# nhd-4_3-adapter.net
KiCad netlist of a schematic drawn in EAGLE
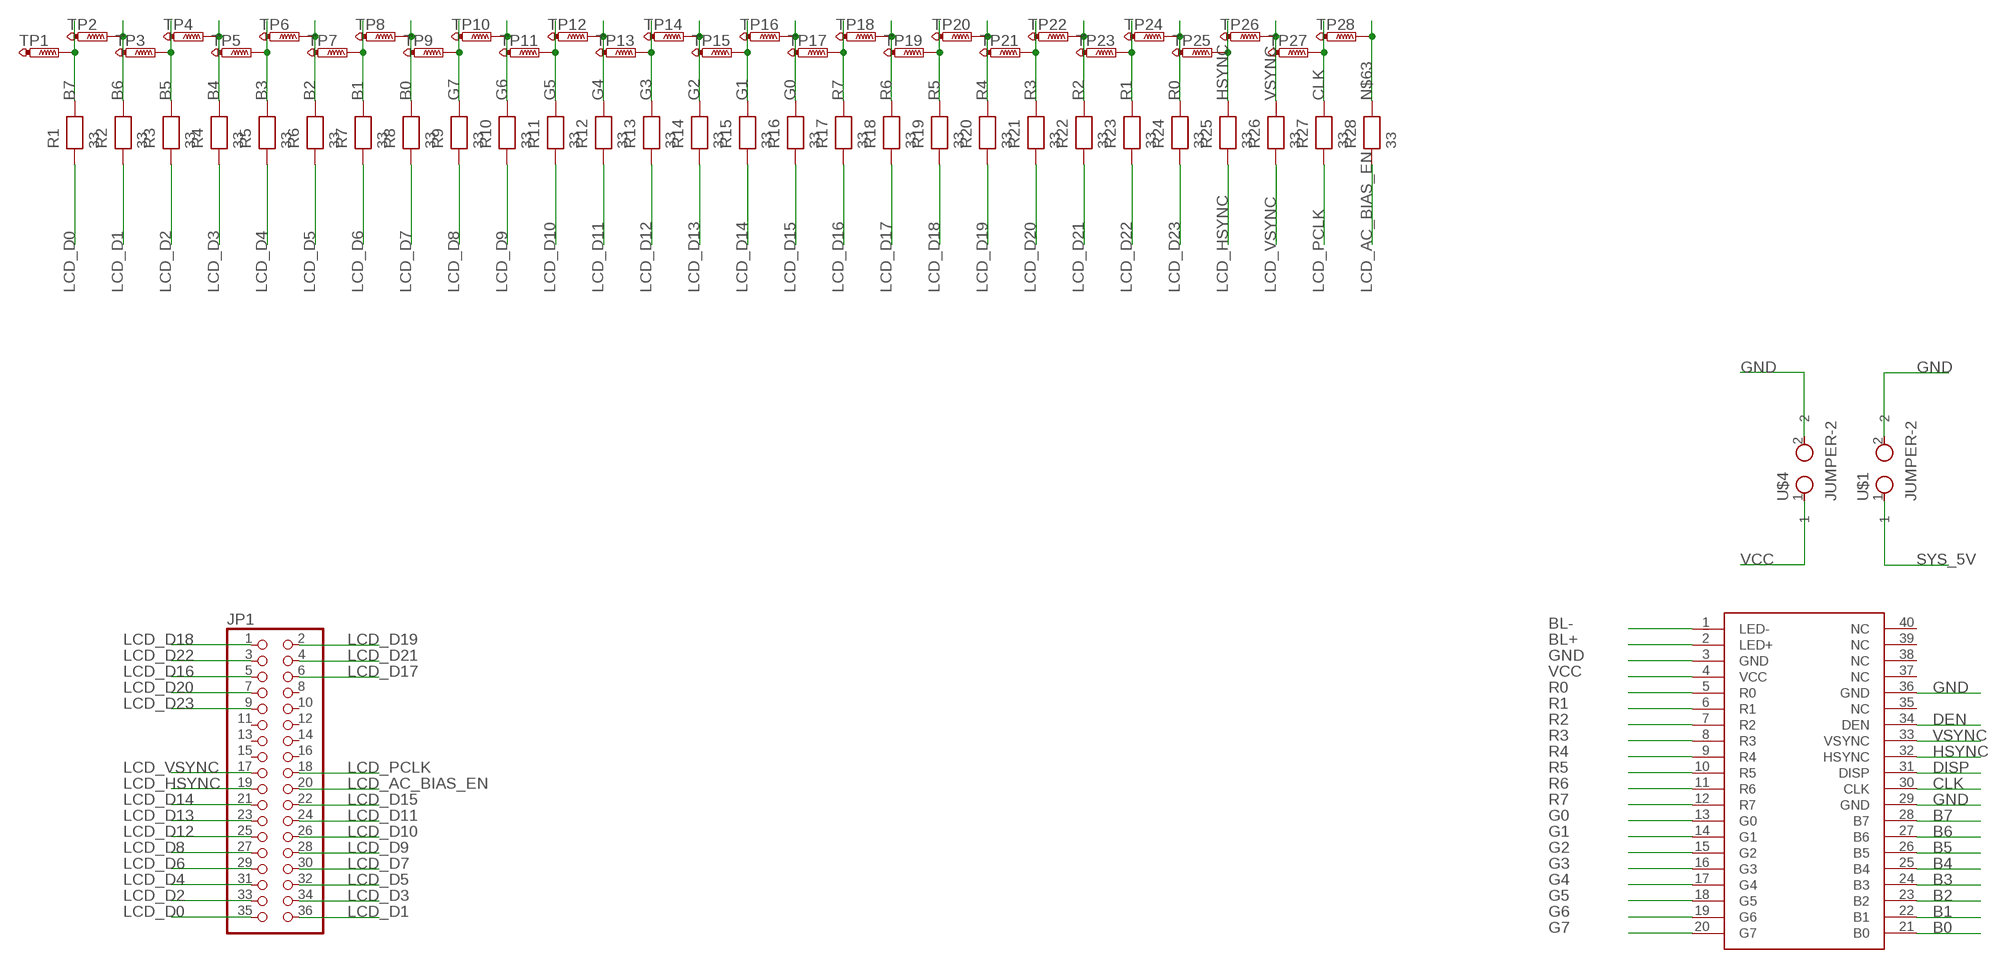
[diagram p0: schematic, sheet 1]
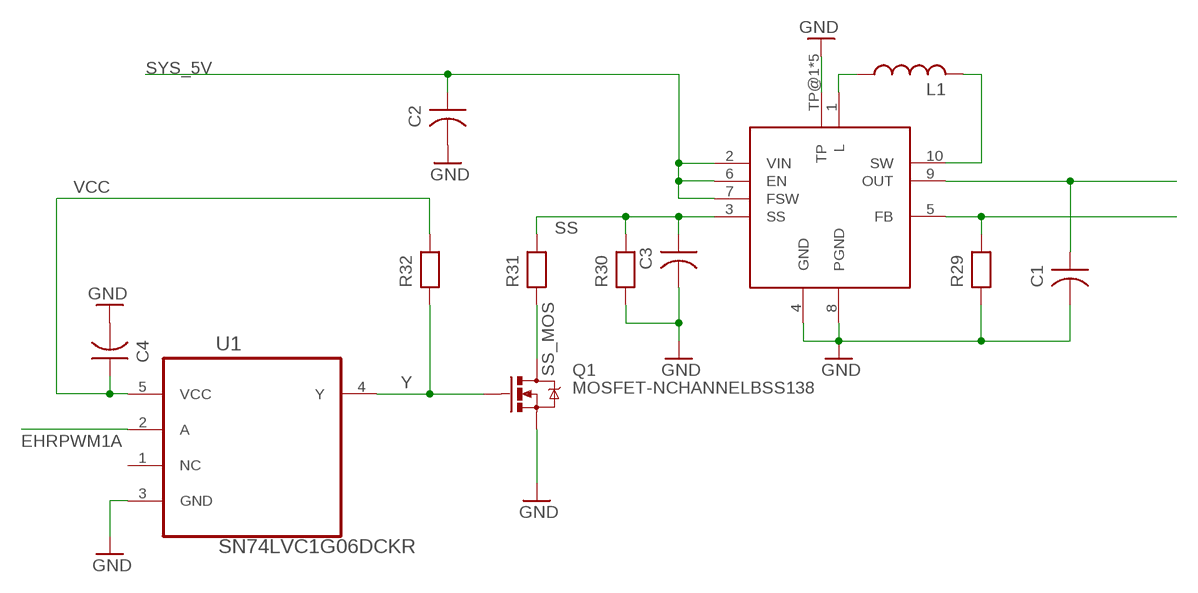
[diagram p1: schematic, sheet 2]

(export (version "E")
  (design (tool "Eeschema 10.0.6"))
  (components
    (comp (ref "JP1")
      (value "PINHD-2X18_2.54")
      (footprint "eagle-import:2X18")
      (libsource (lib "eagle-import") (part "PINHD-2X18_2.54"))
    )
    (comp (ref "R1")
      (value "33")
      (footprint "eagle-import:R0402")
      (libsource (lib "eagle-import") (part "PRES0402LEVEL3"))
    )
    (comp (ref "R2")
      (value "33")
      (footprint "eagle-import:R0402")
      (libsource (lib "eagle-import") (part "PRES0402LEVEL3"))
    )
    (comp (ref "R3")
      (value "33")
      (footprint "eagle-import:R0402")
      (libsource (lib "eagle-import") (part "PRES0402LEVEL3"))
    )
    (comp (ref "R4")
      (value "33")
      (footprint "eagle-import:R0402")
      (libsource (lib "eagle-import") (part "PRES0402LEVEL3"))
    )
    (comp (ref "R5")
      (value "33")
      (footprint "eagle-import:R0402")
      (libsource (lib "eagle-import") (part "PRES0402LEVEL3"))
    )
    (comp (ref "R6")
      (value "33")
      (footprint "eagle-import:R0402")
      (libsource (lib "eagle-import") (part "PRES0402LEVEL3"))
    )
    (comp (ref "R7")
      (value "33")
      (footprint "eagle-import:R0402")
      (libsource (lib "eagle-import") (part "PRES0402LEVEL3"))
    )
    (comp (ref "R8")
      (value "33")
      (footprint "eagle-import:R0402")
      (libsource (lib "eagle-import") (part "PRES0402LEVEL3"))
    )
    (comp (ref "R9")
      (value "33")
      (footprint "eagle-import:R0402")
      (libsource (lib "eagle-import") (part "PRES0402LEVEL3"))
    )
    (comp (ref "R10")
      (value "33")
      (footprint "eagle-import:R0402")
      (libsource (lib "eagle-import") (part "PRES0402LEVEL3"))
    )
    (comp (ref "R11")
      (value "33")
      (footprint "eagle-import:R0402")
      (libsource (lib "eagle-import") (part "PRES0402LEVEL3"))
    )
    (comp (ref "R12")
      (value "33")
      (footprint "eagle-import:R0402")
      (libsource (lib "eagle-import") (part "PRES0402LEVEL3"))
    )
    (comp (ref "R13")
      (value "33")
      (footprint "eagle-import:R0402")
      (libsource (lib "eagle-import") (part "PRES0402LEVEL3"))
    )
    (comp (ref "R14")
      (value "33")
      (footprint "eagle-import:R0402")
      (libsource (lib "eagle-import") (part "PRES0402LEVEL3"))
    )
    (comp (ref "R15")
      (value "33")
      (footprint "eagle-import:R0402")
      (libsource (lib "eagle-import") (part "PRES0402LEVEL3"))
    )
    (comp (ref "R16")
      (value "33")
      (footprint "eagle-import:R0402")
      (libsource (lib "eagle-import") (part "PRES0402LEVEL3"))
    )
    (comp (ref "R17")
      (value "33")
      (footprint "eagle-import:R0402")
      (libsource (lib "eagle-import") (part "PRES0402LEVEL3"))
    )
    (comp (ref "R18")
      (value "33")
      (footprint "eagle-import:R0402")
      (libsource (lib "eagle-import") (part "PRES0402LEVEL3"))
    )
    (comp (ref "R19")
      (value "33")
      (footprint "eagle-import:R0402")
      (libsource (lib "eagle-import") (part "PRES0402LEVEL3"))
    )
    (comp (ref "R20")
      (value "33")
      (footprint "eagle-import:R0402")
      (libsource (lib "eagle-import") (part "PRES0402LEVEL3"))
    )
    (comp (ref "R21")
      (value "33")
      (footprint "eagle-import:R0402")
      (libsource (lib "eagle-import") (part "PRES0402LEVEL3"))
    )
    (comp (ref "R22")
      (value "33")
      (footprint "eagle-import:R0402")
      (libsource (lib "eagle-import") (part "PRES0402LEVEL3"))
    )
    (comp (ref "R23")
      (value "33")
      (footprint "eagle-import:R0402")
      (libsource (lib "eagle-import") (part "PRES0402LEVEL3"))
    )
    (comp (ref "R24")
      (value "33")
      (footprint "eagle-import:R0402")
      (libsource (lib "eagle-import") (part "PRES0402LEVEL3"))
    )
    (comp (ref "R25")
      (value "33")
      (footprint "eagle-import:R0402")
      (libsource (lib "eagle-import") (part "PRES0402LEVEL3"))
    )
    (comp (ref "R26")
      (value "33")
      (footprint "eagle-import:R0402")
      (libsource (lib "eagle-import") (part "PRES0402LEVEL3"))
    )
    (comp (ref "R27")
      (value "33")
      (footprint "eagle-import:R0402")
      (libsource (lib "eagle-import") (part "PRES0402LEVEL3"))
    )
    (comp (ref "R28")
      (value "33")
      (footprint "eagle-import:R0402")
      (libsource (lib "eagle-import") (part "PRES0402LEVEL3"))
    )
    (comp (ref "TFT1")
      (value "NHD-4.3-480272EF-ATXL")
      (footprint "eagle-import:40-PIN_SMD")
      (libsource (lib "eagle-import") (part "NHD-4.3-480272EF-ATXL"))
    )
    (comp (ref "TP1")
      (value "TESTPAD_PTR1TP06R")
      (footprint "eagle-import:TESTPAD_TP06R")
      (libsource (lib "eagle-import") (part "TESTPAD_PTR1TP06R"))
    )
    (comp (ref "TP2")
      (value "TESTPAD_PTR1TP06R")
      (footprint "eagle-import:TESTPAD_TP06R")
      (libsource (lib "eagle-import") (part "TESTPAD_PTR1TP06R"))
    )
    (comp (ref "TP3")
      (value "TESTPAD_PTR1TP06R")
      (footprint "eagle-import:TESTPAD_TP06R")
      (libsource (lib "eagle-import") (part "TESTPAD_PTR1TP06R"))
    )
    (comp (ref "TP4")
      (value "TESTPAD_PTR1TP06R")
      (footprint "eagle-import:TESTPAD_TP06R")
      (libsource (lib "eagle-import") (part "TESTPAD_PTR1TP06R"))
    )
    (comp (ref "TP5")
      (value "TESTPAD_PTR1TP06R")
      (footprint "eagle-import:TESTPAD_TP06R")
      (libsource (lib "eagle-import") (part "TESTPAD_PTR1TP06R"))
    )
    (comp (ref "TP6")
      (value "TESTPAD_PTR1TP06R")
      (footprint "eagle-import:TESTPAD_TP06R")
      (libsource (lib "eagle-import") (part "TESTPAD_PTR1TP06R"))
    )
    (comp (ref "TP7")
      (value "TESTPAD_PTR1TP06R")
      (footprint "eagle-import:TESTPAD_TP06R")
      (libsource (lib "eagle-import") (part "TESTPAD_PTR1TP06R"))
    )
    (comp (ref "TP8")
      (value "TESTPAD_PTR1TP06R")
      (footprint "eagle-import:TESTPAD_TP06R")
      (libsource (lib "eagle-import") (part "TESTPAD_PTR1TP06R"))
    )
    (comp (ref "TP9")
      (value "TESTPAD_PTR1TP06R")
      (footprint "eagle-import:TESTPAD_TP06R")
      (libsource (lib "eagle-import") (part "TESTPAD_PTR1TP06R"))
    )
    (comp (ref "TP10")
      (value "TESTPAD_PTR1TP06R")
      (footprint "eagle-import:TESTPAD_TP06R")
      (libsource (lib "eagle-import") (part "TESTPAD_PTR1TP06R"))
    )
    (comp (ref "TP11")
      (value "TESTPAD_PTR1TP06R")
      (footprint "eagle-import:TESTPAD_TP06R")
      (libsource (lib "eagle-import") (part "TESTPAD_PTR1TP06R"))
    )
    (comp (ref "TP12")
      (value "TESTPAD_PTR1TP06R")
      (footprint "eagle-import:TESTPAD_TP06R")
      (libsource (lib "eagle-import") (part "TESTPAD_PTR1TP06R"))
    )
    (comp (ref "TP13")
      (value "TESTPAD_PTR1TP06R")
      (footprint "eagle-import:TESTPAD_TP06R")
      (libsource (lib "eagle-import") (part "TESTPAD_PTR1TP06R"))
    )
    (comp (ref "TP14")
      (value "TESTPAD_PTR1TP06R")
      (footprint "eagle-import:TESTPAD_TP06R")
      (libsource (lib "eagle-import") (part "TESTPAD_PTR1TP06R"))
    )
    (comp (ref "TP15")
      (value "TESTPAD_PTR1TP06R")
      (footprint "eagle-import:TESTPAD_TP06R")
      (libsource (lib "eagle-import") (part "TESTPAD_PTR1TP06R"))
    )
    (comp (ref "TP16")
      (value "TESTPAD_PTR1TP06R")
      (footprint "eagle-import:TESTPAD_TP06R")
      (libsource (lib "eagle-import") (part "TESTPAD_PTR1TP06R"))
    )
    (comp (ref "TP17")
      (value "TESTPAD_PTR1TP06R")
      (footprint "eagle-import:TESTPAD_TP06R")
      (libsource (lib "eagle-import") (part "TESTPAD_PTR1TP06R"))
    )
    (comp (ref "TP18")
      (value "TESTPAD_PTR1TP06R")
      (footprint "eagle-import:TESTPAD_TP06R")
      (libsource (lib "eagle-import") (part "TESTPAD_PTR1TP06R"))
    )
    (comp (ref "TP19")
      (value "TESTPAD_PTR1TP06R")
      (footprint "eagle-import:TESTPAD_TP06R")
      (libsource (lib "eagle-import") (part "TESTPAD_PTR1TP06R"))
    )
    (comp (ref "TP20")
      (value "TESTPAD_PTR1TP06R")
      (footprint "eagle-import:TESTPAD_TP06R")
      (libsource (lib "eagle-import") (part "TESTPAD_PTR1TP06R"))
    )
    (comp (ref "TP21")
      (value "TESTPAD_PTR1TP06R")
      (footprint "eagle-import:TESTPAD_TP06R")
      (libsource (lib "eagle-import") (part "TESTPAD_PTR1TP06R"))
    )
    (comp (ref "TP22")
      (value "TESTPAD_PTR1TP06R")
      (footprint "eagle-import:TESTPAD_TP06R")
      (libsource (lib "eagle-import") (part "TESTPAD_PTR1TP06R"))
    )
    (comp (ref "TP23")
      (value "TESTPAD_PTR1TP06R")
      (footprint "eagle-import:TESTPAD_TP06R")
      (libsource (lib "eagle-import") (part "TESTPAD_PTR1TP06R"))
    )
    (comp (ref "TP24")
      (value "TESTPAD_PTR1TP06R")
      (footprint "eagle-import:TESTPAD_TP06R")
      (libsource (lib "eagle-import") (part "TESTPAD_PTR1TP06R"))
    )
    (comp (ref "TP25")
      (value "TESTPAD_PTR1TP06R")
      (footprint "eagle-import:TESTPAD_TP06R")
      (libsource (lib "eagle-import") (part "TESTPAD_PTR1TP06R"))
    )
    (comp (ref "TP26")
      (value "TESTPAD_PTR1TP06R")
      (footprint "eagle-import:TESTPAD_TP06R")
      (libsource (lib "eagle-import") (part "TESTPAD_PTR1TP06R"))
    )
    (comp (ref "TP27")
      (value "TESTPAD_PTR1TP06R")
      (footprint "eagle-import:TESTPAD_TP06R")
      (libsource (lib "eagle-import") (part "TESTPAD_PTR1TP06R"))
    )
    (comp (ref "TP28")
      (value "TESTPAD_PTR1TP06R")
      (footprint "eagle-import:TESTPAD_TP06R")
      (libsource (lib "eagle-import") (part "TESTPAD_PTR1TP06R"))
    )
    (comp (ref "U$1")
      (value "JUMPER-2")
      (footprint "eagle-import:1X02")
      (libsource (lib "eagle-import") (part "JUMPER-2"))
    )
    (comp (ref "U$4")
      (value "JUMPER-2")
      (footprint "eagle-import:1X02")
      (libsource (lib "eagle-import") (part "JUMPER-2"))
    )
    (comp (ref "C1")
      (value "PCAP0805LEVEL3")
      (footprint "eagle-import:R0805")
      (libsource (lib "eagle-import") (part "PCAP0805LEVEL3"))
    )
    (comp (ref "C2")
      (value "PCAP0805LEVEL3")
      (footprint "eagle-import:R0805")
      (libsource (lib "eagle-import") (part "PCAP0805LEVEL3"))
    )
    (comp (ref "C3")
      (value "PCAP0603LEVEL3")
      (footprint "eagle-import:R0603")
      (libsource (lib "eagle-import") (part "PCAP0603LEVEL3"))
    )
    (comp (ref "C4")
      (value "PCAP0603LEVEL3")
      (footprint "eagle-import:R0603")
      (libsource (lib "eagle-import") (part "PCAP0603LEVEL3"))
    )
    (comp (ref "L1")
      (value "L-US")
      (footprint "eagle-import:VLCF4018-2")
      (libsource (lib "eagle-import") (part "L-US"))
    )
    (comp (ref "Q1")
      (value "MOSFET-NCHANNELBSS138")
      (footprint "eagle-import:SOT23")
      (libsource (lib "eagle-import") (part "MOSFET-NCHANNELBSS138"))
    )
    (comp (ref "R29")
      (value "PRES0603LEVEL3")
      (footprint "eagle-import:R0603")
      (libsource (lib "eagle-import") (part "PRES0603LEVEL3"))
    )
    (comp (ref "R30")
      (value "PRES0603LEVEL3")
      (footprint "eagle-import:R0603")
      (libsource (lib "eagle-import") (part "PRES0603LEVEL3"))
    )
    (comp (ref "R31")
      (value "PRES0603LEVEL3")
      (footprint "eagle-import:R0603")
      (libsource (lib "eagle-import") (part "PRES0603LEVEL3"))
    )
    (comp (ref "R32")
      (value "PRES0603LEVEL3")
      (footprint "eagle-import:R0603")
      (libsource (lib "eagle-import") (part "PRES0603LEVEL3"))
    )
    (comp (ref "U$2")
      (value "TPS61080")
      (footprint "eagle-import:VSON-10")
      (libsource (lib "eagle-import") (part "TPS61080"))
    )
    (comp (ref "U1")
      (value "SN74LVC1G06DCKR")
      (footprint "eagle-import:SOT65P210X110-5N")
      (libsource (lib "eagle-import") (part "SN74LVC1G06DCKR"))
    )
  )
  (nets
    (net (code "1") (name "B0") (class "Default")
      (node (ref "R8") (pin "P$2") (pinfunction "P$2_P$2") (pintype "bidirectional"))
      (node (ref "TFT1") (pin "21") (pinfunction "B0_21") (pintype "bidirectional"))
      (node (ref "TP8") (pin "TP") (pinfunction "TP_TP") (pintype "input"))
    )
    (net (code "2") (name "B1") (class "Default")
      (node (ref "R7") (pin "P$2") (pinfunction "P$2_P$2") (pintype "bidirectional"))
      (node (ref "TFT1") (pin "22") (pinfunction "B1_22") (pintype "bidirectional"))
      (node (ref "TP7") (pin "TP") (pinfunction "TP_TP") (pintype "input"))
    )
    (net (code "3") (name "B2") (class "Default")
      (node (ref "R6") (pin "P$2") (pinfunction "P$2_P$2") (pintype "bidirectional"))
      (node (ref "TFT1") (pin "23") (pinfunction "B2_23") (pintype "bidirectional"))
      (node (ref "TP6") (pin "TP") (pinfunction "TP_TP") (pintype "input"))
    )
    (net (code "4") (name "B3") (class "Default")
      (node (ref "R5") (pin "P$2") (pinfunction "P$2_P$2") (pintype "bidirectional"))
      (node (ref "TFT1") (pin "24") (pinfunction "B3_24") (pintype "bidirectional"))
      (node (ref "TP5") (pin "TP") (pinfunction "TP_TP") (pintype "input"))
    )
    (net (code "5") (name "B4") (class "Default")
      (node (ref "R4") (pin "P$2") (pinfunction "P$2_P$2") (pintype "bidirectional"))
      (node (ref "TFT1") (pin "25") (pinfunction "B4_25") (pintype "bidirectional"))
      (node (ref "TP4") (pin "TP") (pinfunction "TP_TP") (pintype "input"))
    )
    (net (code "6") (name "B5") (class "Default")
      (node (ref "R3") (pin "P$2") (pinfunction "P$2_P$2") (pintype "bidirectional"))
      (node (ref "TFT1") (pin "26") (pinfunction "B5_26") (pintype "bidirectional"))
      (node (ref "TP3") (pin "TP") (pinfunction "TP_TP") (pintype "input"))
    )
    (net (code "7") (name "B6") (class "Default")
      (node (ref "R2") (pin "P$2") (pinfunction "P$2_P$2") (pintype "bidirectional"))
      (node (ref "TFT1") (pin "27") (pinfunction "B6_27") (pintype "bidirectional"))
      (node (ref "TP2") (pin "TP") (pinfunction "TP_TP") (pintype "input"))
    )
    (net (code "8") (name "B7") (class "Default")
      (node (ref "R1") (pin "P$2") (pinfunction "P$2_P$2") (pintype "bidirectional"))
      (node (ref "TFT1") (pin "28") (pinfunction "B7_28") (pintype "bidirectional"))
      (node (ref "TP1") (pin "TP") (pinfunction "TP_TP") (pintype "input"))
    )
    (net (code "9") (name "BL+") (class "Default")
      (node (ref "C1") (pin "P$2") (pinfunction "P$2_P$2") (pintype "bidirectional"))
      (node (ref "TFT1") (pin "2") (pinfunction "LED+_2") (pintype "bidirectional"))
      (node (ref "U$2") (pin "9") (pinfunction "OUT_9") (pintype "bidirectional"))
    )
    (net (code "10") (name "BL-") (class "Default")
      (node (ref "R29") (pin "P$2") (pinfunction "P$2_P$2") (pintype "bidirectional"))
      (node (ref "TFT1") (pin "1") (pinfunction "LED-_1") (pintype "bidirectional"))
      (node (ref "U$2") (pin "5") (pinfunction "FB_5") (pintype "bidirectional"))
    )
    (net (code "11") (name "CLK") (class "Default")
      (node (ref "R27") (pin "P$2") (pinfunction "P$2_P$2") (pintype "bidirectional"))
      (node (ref "TFT1") (pin "30") (pinfunction "CLK_30") (pintype "bidirectional"))
      (node (ref "TP27") (pin "TP") (pinfunction "TP_TP") (pintype "input"))
    )
    (net (code "12") (name "DEN") (class "Default")
      (node (ref "TFT1") (pin "34") (pinfunction "DEN_34") (pintype "bidirectional"))
    )
    (net (code "13") (name "DISP") (class "Default")
      (node (ref "TFT1") (pin "31") (pinfunction "DISP_31") (pintype "bidirectional"))
    )
    (net (code "14") (name "EHRPWM1A") (class "Default")
      (node (ref "U1") (pin "2") (pinfunction "A_2") (pintype "input"))
    )
    (net (code "15") (name "G0") (class "Default")
      (node (ref "R16") (pin "P$2") (pinfunction "P$2_P$2") (pintype "bidirectional"))
      (node (ref "TFT1") (pin "13") (pinfunction "G0_13") (pintype "bidirectional"))
      (node (ref "TP16") (pin "TP") (pinfunction "TP_TP") (pintype "input"))
    )
    (net (code "16") (name "G1") (class "Default")
      (node (ref "R15") (pin "P$2") (pinfunction "P$2_P$2") (pintype "bidirectional"))
      (node (ref "TFT1") (pin "14") (pinfunction "G1_14") (pintype "bidirectional"))
      (node (ref "TP15") (pin "TP") (pinfunction "TP_TP") (pintype "input"))
    )
    (net (code "17") (name "G2") (class "Default")
      (node (ref "R14") (pin "P$2") (pinfunction "P$2_P$2") (pintype "bidirectional"))
      (node (ref "TFT1") (pin "15") (pinfunction "G2_15") (pintype "bidirectional"))
      (node (ref "TP14") (pin "TP") (pinfunction "TP_TP") (pintype "input"))
    )
    (net (code "18") (name "G3") (class "Default")
      (node (ref "R13") (pin "P$2") (pinfunction "P$2_P$2") (pintype "bidirectional"))
      (node (ref "TFT1") (pin "16") (pinfunction "G3_16") (pintype "bidirectional"))
      (node (ref "TP13") (pin "TP") (pinfunction "TP_TP") (pintype "input"))
    )
    (net (code "19") (name "G4") (class "Default")
      (node (ref "R12") (pin "P$2") (pinfunction "P$2_P$2") (pintype "bidirectional"))
      (node (ref "TFT1") (pin "17") (pinfunction "G4_17") (pintype "bidirectional"))
      (node (ref "TP12") (pin "TP") (pinfunction "TP_TP") (pintype "input"))
    )
    (net (code "20") (name "G5") (class "Default")
      (node (ref "R11") (pin "P$2") (pinfunction "P$2_P$2") (pintype "bidirectional"))
      (node (ref "TFT1") (pin "18") (pinfunction "G5_18") (pintype "bidirectional"))
      (node (ref "TP11") (pin "TP") (pinfunction "TP_TP") (pintype "input"))
    )
    (net (code "21") (name "G6") (class "Default")
      (node (ref "R10") (pin "P$2") (pinfunction "P$2_P$2") (pintype "bidirectional"))
      (node (ref "TFT1") (pin "19") (pinfunction "G6_19") (pintype "bidirectional"))
      (node (ref "TP10") (pin "TP") (pinfunction "TP_TP") (pintype "input"))
    )
    (net (code "22") (name "G7") (class "Default")
      (node (ref "R9") (pin "P$2") (pinfunction "P$2_P$2") (pintype "bidirectional"))
      (node (ref "TFT1") (pin "20") (pinfunction "G7_20") (pintype "bidirectional"))
      (node (ref "TP9") (pin "TP") (pinfunction "TP_TP") (pintype "input"))
    )
    (net (code "23") (name "GND") (class "Default")
      (node (ref "C1") (pin "P$1") (pinfunction "P$1_P$1") (pintype "bidirectional"))
      (node (ref "C2") (pin "P$1") (pinfunction "P$1_P$1") (pintype "bidirectional"))
      (node (ref "C3") (pin "P$1") (pinfunction "P$1_P$1") (pintype "bidirectional"))
      (node (ref "C4") (pin "P$1") (pinfunction "P$1_P$1") (pintype "bidirectional"))
      (node (ref "Q1") (pin "2") (pinfunction "S_2") (pintype "passive"))
      (node (ref "R29") (pin "P$1") (pinfunction "P$1_P$1") (pintype "bidirectional"))
      (node (ref "R30") (pin "P$1") (pinfunction "P$1_P$1") (pintype "bidirectional"))
      (node (ref "TFT1") (pin "29") (pinfunction "GND_29") (pintype "bidirectional"))
      (node (ref "TFT1") (pin "3") (pinfunction "GND_3") (pintype "bidirectional"))
      (node (ref "TFT1") (pin "36") (pinfunction "GND_36") (pintype "bidirectional"))
      (node (ref "U$1") (pin "2") (pinfunction "2_2") (pintype "bidirectional"))
      (node (ref "U$2") (pin "4") (pinfunction "GND_4") (pintype "bidirectional"))
      (node (ref "U$2") (pin "8") (pinfunction "PGND_8") (pintype "bidirectional"))
      (node (ref "U$2") (pin "TP@1") (pinfunction "TP_TP@1") (pintype "bidirectional"))
      (node (ref "U$2") (pin "TP@2") (pinfunction "TP_TP@2") (pintype "bidirectional"))
      (node (ref "U$2") (pin "TP@3") (pinfunction "TP_TP@3") (pintype "bidirectional"))
      (node (ref "U$2") (pin "TP@4") (pinfunction "TP_TP@4") (pintype "bidirectional"))
      (node (ref "U$2") (pin "TP@5") (pinfunction "TP_TP@5") (pintype "bidirectional"))
      (node (ref "U$4") (pin "2") (pinfunction "2_2") (pintype "bidirectional"))
      (node (ref "U1") (pin "3") (pinfunction "GND_3") (pintype "passive"))
    )
    (net (code "24") (name "HSYNC") (class "Default")
      (node (ref "R25") (pin "P$2") (pinfunction "P$2_P$2") (pintype "bidirectional"))
      (node (ref "TFT1") (pin "32") (pinfunction "HSYNC_32") (pintype "bidirectional"))
      (node (ref "TP25") (pin "TP") (pinfunction "TP_TP") (pintype "input"))
    )
    (net (code "25") (name "LCD_AC_BIAS_EN") (class "Default")
      (node (ref "JP1") (pin "20") (pinfunction "20_20") (pintype "passive"))
      (node (ref "R28") (pin "P$1") (pinfunction "P$1_P$1") (pintype "bidirectional"))
    )
    (net (code "26") (name "LCD_D0") (class "Default")
      (node (ref "JP1") (pin "35") (pinfunction "35_35") (pintype "passive"))
      (node (ref "R1") (pin "P$1") (pinfunction "P$1_P$1") (pintype "bidirectional"))
    )
    (net (code "27") (name "LCD_D1") (class "Default")
      (node (ref "JP1") (pin "36") (pinfunction "36_36") (pintype "passive"))
      (node (ref "R2") (pin "P$1") (pinfunction "P$1_P$1") (pintype "bidirectional"))
    )
    (net (code "28") (name "LCD_D2") (class "Default")
      (node (ref "JP1") (pin "33") (pinfunction "33_33") (pintype "passive"))
      (node (ref "R3") (pin "P$1") (pinfunction "P$1_P$1") (pintype "bidirectional"))
    )
    (net (code "29") (name "LCD_D3") (class "Default")
      (node (ref "JP1") (pin "34") (pinfunction "34_34") (pintype "passive"))
      (node (ref "R4") (pin "P$1") (pinfunction "P$1_P$1") (pintype "bidirectional"))
    )
    (net (code "30") (name "LCD_D4") (class "Default")
      (node (ref "JP1") (pin "31") (pinfunction "31_31") (pintype "passive"))
      (node (ref "R5") (pin "P$1") (pinfunction "P$1_P$1") (pintype "bidirectional"))
    )
    (net (code "31") (name "LCD_D5") (class "Default")
      (node (ref "JP1") (pin "32") (pinfunction "32_32") (pintype "passive"))
      (node (ref "R6") (pin "P$1") (pinfunction "P$1_P$1") (pintype "bidirectional"))
    )
    (net (code "32") (name "LCD_D6") (class "Default")
      (node (ref "JP1") (pin "29") (pinfunction "29_29") (pintype "passive"))
      (node (ref "R7") (pin "P$1") (pinfunction "P$1_P$1") (pintype "bidirectional"))
    )
    (net (code "33") (name "LCD_D7") (class "Default")
      (node (ref "JP1") (pin "30") (pinfunction "30_30") (pintype "passive"))
      (node (ref "R8") (pin "P$1") (pinfunction "P$1_P$1") (pintype "bidirectional"))
    )
    (net (code "34") (name "LCD_D8") (class "Default")
      (node (ref "JP1") (pin "27") (pinfunction "27_27") (pintype "passive"))
      (node (ref "R9") (pin "P$1") (pinfunction "P$1_P$1") (pintype "bidirectional"))
    )
    (net (code "35") (name "LCD_D9") (class "Default")
      (node (ref "JP1") (pin "28") (pinfunction "28_28") (pintype "passive"))
      (node (ref "R10") (pin "P$1") (pinfunction "P$1_P$1") (pintype "bidirectional"))
    )
    (net (code "36") (name "LCD_D10") (class "Default")
      (node (ref "JP1") (pin "26") (pinfunction "26_26") (pintype "passive"))
      (node (ref "R11") (pin "P$1") (pinfunction "P$1_P$1") (pintype "bidirectional"))
    )
    (net (code "37") (name "LCD_D11") (class "Default")
      (node (ref "JP1") (pin "24") (pinfunction "24_24") (pintype "passive"))
      (node (ref "R12") (pin "P$1") (pinfunction "P$1_P$1") (pintype "bidirectional"))
    )
    (net (code "38") (name "LCD_D12") (class "Default")
      (node (ref "JP1") (pin "25") (pinfunction "25_25") (pintype "passive"))
      (node (ref "R13") (pin "P$1") (pinfunction "P$1_P$1") (pintype "bidirectional"))
    )
    (net (code "39") (name "LCD_D13") (class "Default")
      (node (ref "JP1") (pin "23") (pinfunction "23_23") (pintype "passive"))
      (node (ref "R14") (pin "P$1") (pinfunction "P$1_P$1") (pintype "bidirectional"))
    )
    (net (code "40") (name "LCD_D14") (class "Default")
      (node (ref "JP1") (pin "21") (pinfunction "21_21") (pintype "passive"))
      (node (ref "R15") (pin "P$1") (pinfunction "P$1_P$1") (pintype "bidirectional"))
    )
    (net (code "41") (name "LCD_D15") (class "Default")
      (node (ref "JP1") (pin "22") (pinfunction "22_22") (pintype "passive"))
      (node (ref "R16") (pin "P$1") (pinfunction "P$1_P$1") (pintype "bidirectional"))
    )
    (net (code "42") (name "LCD_D16") (class "Default")
      (node (ref "JP1") (pin "5") (pinfunction "5_5") (pintype "passive"))
      (node (ref "R17") (pin "P$1") (pinfunction "P$1_P$1") (pintype "bidirectional"))
    )
    (net (code "43") (name "LCD_D17") (class "Default")
      (node (ref "JP1") (pin "6") (pinfunction "6_6") (pintype "passive"))
      (node (ref "R18") (pin "P$1") (pinfunction "P$1_P$1") (pintype "bidirectional"))
    )
    (net (code "44") (name "LCD_D18") (class "Default")
      (node (ref "JP1") (pin "1") (pinfunction "1_1") (pintype "passive"))
      (node (ref "R19") (pin "P$1") (pinfunction "P$1_P$1") (pintype "bidirectional"))
    )
    (net (code "45") (name "LCD_D19") (class "Default")
      (node (ref "JP1") (pin "2") (pinfunction "2_2") (pintype "passive"))
      (node (ref "R20") (pin "P$1") (pinfunction "P$1_P$1") (pintype "bidirectional"))
    )
    (net (code "46") (name "LCD_D20") (class "Default")
      (node (ref "JP1") (pin "7") (pinfunction "7_7") (pintype "passive"))
      (node (ref "R21") (pin "P$1") (pinfunction "P$1_P$1") (pintype "bidirectional"))
    )
    (net (code "47") (name "LCD_D21") (class "Default")
      (node (ref "JP1") (pin "4") (pinfunction "4_4") (pintype "passive"))
      (node (ref "R22") (pin "P$1") (pinfunction "P$1_P$1") (pintype "bidirectional"))
    )
    (net (code "48") (name "LCD_D22") (class "Default")
      (node (ref "JP1") (pin "3") (pinfunction "3_3") (pintype "passive"))
      (node (ref "R23") (pin "P$1") (pinfunction "P$1_P$1") (pintype "bidirectional"))
    )
    (net (code "49") (name "LCD_D23") (class "Default")
      (node (ref "JP1") (pin "9") (pinfunction "9_9") (pintype "passive"))
      (node (ref "R24") (pin "P$1") (pinfunction "P$1_P$1") (pintype "bidirectional"))
    )
    (net (code "50") (name "LCD_HSYNC") (class "Default")
      (node (ref "JP1") (pin "19") (pinfunction "19_19") (pintype "passive"))
      (node (ref "R25") (pin "P$1") (pinfunction "P$1_P$1") (pintype "bidirectional"))
    )
    (net (code "51") (name "LCD_PCLK") (class "Default")
      (node (ref "JP1") (pin "18") (pinfunction "18_18") (pintype "passive"))
      (node (ref "R27") (pin "P$1") (pinfunction "P$1_P$1") (pintype "bidirectional"))
    )
    (net (code "52") (name "LCD_VSYNC") (class "Default")
      (node (ref "JP1") (pin "17") (pinfunction "17_17") (pintype "passive"))
      (node (ref "R26") (pin "P$1") (pinfunction "P$1_P$1") (pintype "bidirectional"))
    )
    (net (code "53") (name "N$63") (class "Default")
      (node (ref "R28") (pin "P$2") (pinfunction "P$2_P$2") (pintype "bidirectional"))
      (node (ref "TP28") (pin "TP") (pinfunction "TP_TP") (pintype "input"))
    )
    (net (code "54") (name "Net-(U$2-L)") (class "Default")
      (node (ref "L1") (pin "1") (pinfunction "1_1") (pintype "passive"))
      (node (ref "U$2") (pin "1") (pinfunction "L_1") (pintype "bidirectional"))
    )
    (net (code "55") (name "Net-(U$2-SW)") (class "Default")
      (node (ref "L1") (pin "2") (pinfunction "2_2") (pintype "passive"))
      (node (ref "U$2") (pin "10") (pinfunction "SW_10") (pintype "bidirectional"))
    )
    (net (code "56") (name "R0") (class "Default")
      (node (ref "R24") (pin "P$2") (pinfunction "P$2_P$2") (pintype "bidirectional"))
      (node (ref "TFT1") (pin "5") (pinfunction "R0_5") (pintype "bidirectional"))
      (node (ref "TP24") (pin "TP") (pinfunction "TP_TP") (pintype "input"))
    )
    (net (code "57") (name "R1") (class "Default")
      (node (ref "R23") (pin "P$2") (pinfunction "P$2_P$2") (pintype "bidirectional"))
      (node (ref "TFT1") (pin "6") (pinfunction "R1_6") (pintype "bidirectional"))
      (node (ref "TP23") (pin "TP") (pinfunction "TP_TP") (pintype "input"))
    )
    (net (code "58") (name "R2") (class "Default")
      (node (ref "R22") (pin "P$2") (pinfunction "P$2_P$2") (pintype "bidirectional"))
      (node (ref "TFT1") (pin "7") (pinfunction "R2_7") (pintype "bidirectional"))
      (node (ref "TP22") (pin "TP") (pinfunction "TP_TP") (pintype "input"))
    )
    (net (code "59") (name "R3") (class "Default")
      (node (ref "R21") (pin "P$2") (pinfunction "P$2_P$2") (pintype "bidirectional"))
      (node (ref "TFT1") (pin "8") (pinfunction "R3_8") (pintype "bidirectional"))
      (node (ref "TP21") (pin "TP") (pinfunction "TP_TP") (pintype "input"))
    )
    (net (code "60") (name "R4") (class "Default")
      (node (ref "R20") (pin "P$2") (pinfunction "P$2_P$2") (pintype "bidirectional"))
      (node (ref "TFT1") (pin "9") (pinfunction "R4_9") (pintype "bidirectional"))
      (node (ref "TP20") (pin "TP") (pinfunction "TP_TP") (pintype "input"))
    )
    (net (code "61") (name "R5") (class "Default")
      (node (ref "R19") (pin "P$2") (pinfunction "P$2_P$2") (pintype "bidirectional"))
      (node (ref "TFT1") (pin "10") (pinfunction "R5_10") (pintype "bidirectional"))
      (node (ref "TP19") (pin "TP") (pinfunction "TP_TP") (pintype "input"))
    )
    (net (code "62") (name "R6") (class "Default")
      (node (ref "R18") (pin "P$2") (pinfunction "P$2_P$2") (pintype "bidirectional"))
      (node (ref "TFT1") (pin "11") (pinfunction "R6_11") (pintype "bidirectional"))
      (node (ref "TP18") (pin "TP") (pinfunction "TP_TP") (pintype "input"))
    )
    (net (code "63") (name "R7") (class "Default")
      (node (ref "R17") (pin "P$2") (pinfunction "P$2_P$2") (pintype "bidirectional"))
      (node (ref "TFT1") (pin "12") (pinfunction "R7_12") (pintype "bidirectional"))
      (node (ref "TP17") (pin "TP") (pinfunction "TP_TP") (pintype "input"))
    )
    (net (code "64") (name "SS") (class "Default")
      (node (ref "C3") (pin "P$2") (pinfunction "P$2_P$2") (pintype "bidirectional"))
      (node (ref "R30") (pin "P$2") (pinfunction "P$2_P$2") (pintype "bidirectional"))
      (node (ref "R31") (pin "P$2") (pinfunction "P$2_P$2") (pintype "bidirectional"))
      (node (ref "U$2") (pin "3") (pinfunction "SS_3") (pintype "bidirectional"))
    )
    (net (code "65") (name "SS_MOS") (class "Default")
      (node (ref "Q1") (pin "3") (pinfunction "D_3") (pintype "passive"))
      (node (ref "R31") (pin "P$1") (pinfunction "P$1_P$1") (pintype "bidirectional"))
    )
    (net (code "66") (name "SYS_5V") (class "Default")
      (node (ref "C2") (pin "P$2") (pinfunction "P$2_P$2") (pintype "bidirectional"))
      (node (ref "U$1") (pin "1") (pinfunction "1_1") (pintype "bidirectional"))
      (node (ref "U$2") (pin "2") (pinfunction "VIN_2") (pintype "bidirectional"))
      (node (ref "U$2") (pin "6") (pinfunction "EN_6") (pintype "bidirectional"))
      (node (ref "U$2") (pin "7") (pinfunction "FSW_7") (pintype "bidirectional"))
    )
    (net (code "67") (name "VCC") (class "Default")
      (node (ref "C4") (pin "P$2") (pinfunction "P$2_P$2") (pintype "bidirectional"))
      (node (ref "R32") (pin "P$2") (pinfunction "P$2_P$2") (pintype "bidirectional"))
      (node (ref "TFT1") (pin "4") (pinfunction "VCC_4") (pintype "bidirectional"))
      (node (ref "U$4") (pin "1") (pinfunction "1_1") (pintype "bidirectional"))
      (node (ref "U1") (pin "5") (pinfunction "VCC_5") (pintype "power_in"))
    )
    (net (code "68") (name "VSYNC") (class "Default")
      (node (ref "R26") (pin "P$2") (pinfunction "P$2_P$2") (pintype "bidirectional"))
      (node (ref "TFT1") (pin "33") (pinfunction "VSYNC_33") (pintype "bidirectional"))
      (node (ref "TP26") (pin "TP") (pinfunction "TP_TP") (pintype "input"))
    )
    (net (code "69") (name "Y") (class "Default")
      (node (ref "Q1") (pin "1") (pinfunction "G_1") (pintype "passive"))
      (node (ref "R32") (pin "P$1") (pinfunction "P$1_P$1") (pintype "bidirectional"))
      (node (ref "U1") (pin "4") (pinfunction "Y_4") (pintype "output"))
    )
    (net (code "70") (name "unconnected-(JP1-Pad8)") (class "Default")
      (node (ref "JP1") (pin "8") (pinfunction "8_8") (pintype "passive"))
    )
    (net (code "71") (name "unconnected-(JP1-Pad10)") (class "Default")
      (node (ref "JP1") (pin "10") (pinfunction "10_10") (pintype "passive"))
    )
    (net (code "72") (name "unconnected-(JP1-Pad11)") (class "Default")
      (node (ref "JP1") (pin "11") (pinfunction "11_11") (pintype "passive"))
    )
    (net (code "73") (name "unconnected-(JP1-Pad12)") (class "Default")
      (node (ref "JP1") (pin "12") (pinfunction "12_12") (pintype "passive"))
    )
    (net (code "74") (name "unconnected-(JP1-Pad13)") (class "Default")
      (node (ref "JP1") (pin "13") (pinfunction "13_13") (pintype "passive"))
    )
    (net (code "75") (name "unconnected-(JP1-Pad14)") (class "Default")
      (node (ref "JP1") (pin "14") (pinfunction "14_14") (pintype "passive"))
    )
    (net (code "76") (name "unconnected-(JP1-Pad15)") (class "Default")
      (node (ref "JP1") (pin "15") (pinfunction "15_15") (pintype "passive"))
    )
    (net (code "77") (name "unconnected-(JP1-Pad16)") (class "Default")
      (node (ref "JP1") (pin "16") (pinfunction "16_16") (pintype "passive"))
    )
    (net (code "78") (name "unconnected-(TFT1-NC-Pad35)") (class "Default")
      (node (ref "TFT1") (pin "35") (pinfunction "NC_35") (pintype "bidirectional"))
    )
    (net (code "79") (name "unconnected-(TFT1-NC-Pad37)") (class "Default")
      (node (ref "TFT1") (pin "37") (pinfunction "NC_37") (pintype "bidirectional"))
    )
    (net (code "80") (name "unconnected-(TFT1-NC-Pad38)") (class "Default")
      (node (ref "TFT1") (pin "38") (pinfunction "NC_38") (pintype "bidirectional"))
    )
    (net (code "81") (name "unconnected-(TFT1-NC-Pad39)") (class "Default")
      (node (ref "TFT1") (pin "39") (pinfunction "NC_39") (pintype "bidirectional"))
    )
    (net (code "82") (name "unconnected-(TFT1-NC-Pad40)") (class "Default")
      (node (ref "TFT1") (pin "40") (pinfunction "NC_40") (pintype "bidirectional"))
    )
    (net (code "83") (name "unconnected-(U1-NC-Pad1)") (class "Default")
      (node (ref "U1") (pin "1") (pinfunction "NC_1") (pintype "no_connect"))
    )
  )
)
